# Sensirion_flowSensor.net
KiCad netlist of a schematic drawn in EAGLE
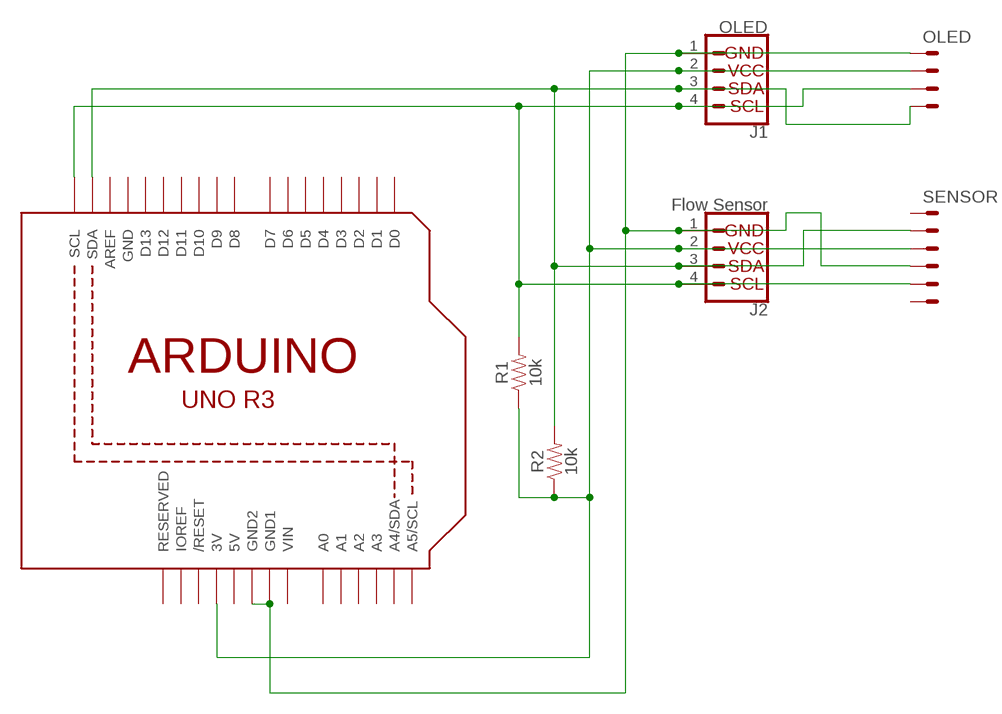
[diagram p0: schematic, sheet 1]

(export (version "E")
  (design (tool "Eeschema 10.0.6"))
  (components
    (comp (ref "FLOW")
      (value "SENSOR")
      (footprint "eagle-import:KK-156-6")
      (fields (field (name "MF") "MOLEX"))
      (libsource (lib "eagle-import") (part "KK-156-6"))
    )
    (comp (ref "J1")
      (value "OLED")
      (footprint "eagle-import:JST04_1MM_VERT")
      (libsource (lib "eagle-import") (part "QWIIC_CONNECTOR"))
    )
    (comp (ref "J2")
      (value "Flow Sensor")
      (footprint "eagle-import:JST04_1MM_VERT")
      (libsource (lib "eagle-import") (part "QWIIC_CONNECTOR"))
    )
    (comp (ref "OLED")
      (value "OLED")
      (footprint "eagle-import:KK-156-4")
      (fields (field (name "MF") "MOLEX"))
      (libsource (lib "eagle-import") (part "KK-156-4"))
    )
    (comp (ref "R1")
      (value "10k")
      (footprint "eagle-import:AXIAL-0.1")
      (libsource (lib "eagle-import") (part "10KOHM-VERT-1/4W-1%"))
    )
    (comp (ref "R2")
      (value "10k")
      (footprint "eagle-import:AXIAL-0.1")
      (libsource (lib "eagle-import") (part "10KOHM-VERT-1/4W-1%"))
    )
    (comp (ref "U1")
      (value "ARDUINOR3-BPLACE")
      (footprint "eagle-import:ARDUINOR3-BPLACE")
      (libsource (lib "eagle-import") (part "ARDUINOR3-BPLACE"))
    )
  )
  (nets
    (net (code "1") (name "/5V") (class "Default")
      (node (ref "U1") (pin "5V") (pinfunction "5V_5V") (pintype "power_in"))
    )
    (net (code "2") (name "/GND") (class "Default")
      (node (ref "U1") (pin "GND") (pinfunction "GND_GND") (pintype "power_in"))
    )
    (net (code "3") (name "/VIN") (class "Default")
      (node (ref "U1") (pin "VIN") (pinfunction "VIN_VIN") (pintype "power_in"))
    )
    (net (code "4") (name "Net-(FLOWB-S)") (class "Default")
      (node (ref "FLOW") (pin "2") (pinfunction "S_2") (pintype "passive"))
      (node (ref "J1") (pin "3") (pinfunction "3_3") (pintype "passive"))
      (node (ref "J2") (pin "3") (pinfunction "3_3") (pintype "passive"))
      (node (ref "OLED") (pin "4") (pinfunction "S_4") (pintype "passive"))
      (node (ref "R2") (pin "P$2") (pinfunction "2_P$2") (pintype "passive"))
      (node (ref "U1") (pin "SDA") (pinfunction "SDA_SDA") (pintype "bidirectional"))
    )
    (net (code "5") (name "Net-(FLOWC-S)") (class "Default")
      (node (ref "FLOW") (pin "3") (pinfunction "S_3") (pintype "passive"))
      (node (ref "J1") (pin "2") (pinfunction "2_2") (pintype "power_in"))
      (node (ref "J2") (pin "2") (pinfunction "2_2") (pintype "power_in"))
      (node (ref "OLED") (pin "2") (pinfunction "S_2") (pintype "passive"))
      (node (ref "R1") (pin "P$1") (pinfunction "1_P$1") (pintype "passive"))
      (node (ref "R2") (pin "P$1") (pinfunction "1_P$1") (pintype "passive"))
      (node (ref "U1") (pin "3V") (pinfunction "3V_3V") (pintype "power_in"))
    )
    (net (code "6") (name "Net-(FLOWD-S)") (class "Default")
      (node (ref "FLOW") (pin "4") (pinfunction "S_4") (pintype "passive"))
      (node (ref "J1") (pin "1") (pinfunction "1_1") (pintype "power_in"))
      (node (ref "J2") (pin "1") (pinfunction "1_1") (pintype "power_in"))
      (node (ref "OLED") (pin "1") (pinfunction "S_1") (pintype "passive"))
      (node (ref "U1") (pin "GND1") (pinfunction "GND1_GND1") (pintype "power_in"))
      (node (ref "U1") (pin "GND2") (pinfunction "GND2_GND2") (pintype "power_in"))
    )
    (net (code "7") (name "Net-(FLOWE-S)") (class "Default")
      (node (ref "FLOW") (pin "5") (pinfunction "S_5") (pintype "passive"))
      (node (ref "J1") (pin "4") (pinfunction "4_4") (pintype "passive"))
      (node (ref "J2") (pin "4") (pinfunction "4_4") (pintype "passive"))
      (node (ref "OLED") (pin "3") (pinfunction "S_3") (pintype "passive"))
      (node (ref "R1") (pin "P$2") (pinfunction "2_P$2") (pintype "passive"))
      (node (ref "U1") (pin "SCL") (pinfunction "SCL_SCL") (pintype "bidirectional"))
    )
    (net (code "8") (name "unconnected-(FLOWA-S-Pad1)") (class "Default")
      (node (ref "FLOW") (pin "1") (pinfunction "S_1") (pintype "passive"))
    )
    (net (code "9") (name "unconnected-(FLOWF-S-Pad6)") (class "Default")
      (node (ref "FLOW") (pin "6") (pinfunction "S_6") (pintype "passive"))
    )
    (net (code "10") (name "unconnected-(U1-A4{slash}SDA-PadA4)") (class "Default")
      (node (ref "U1") (pin "A4") (pinfunction "A4/SDA_A4") (pintype "bidirectional"))
    )
    (net (code "11") (name "unconnected-(U1-A5{slash}SCL-PadA5)") (class "Default")
      (node (ref "U1") (pin "A5") (pinfunction "A5/SCL_A5") (pintype "bidirectional"))
    )
    (net (code "12") (name "unconnected-(U1-PadA0)") (class "Default")
      (node (ref "U1") (pin "A0") (pinfunction "A0_A0") (pintype "bidirectional"))
    )
    (net (code "13") (name "unconnected-(U1-PadA1)") (class "Default")
      (node (ref "U1") (pin "A1") (pinfunction "A1_A1") (pintype "bidirectional"))
    )
    (net (code "14") (name "unconnected-(U1-PadA2)") (class "Default")
      (node (ref "U1") (pin "A2") (pinfunction "A2_A2") (pintype "bidirectional"))
    )
    (net (code "15") (name "unconnected-(U1-PadA3)") (class "Default")
      (node (ref "U1") (pin "A3") (pinfunction "A3_A3") (pintype "bidirectional"))
    )
    (net (code "16") (name "unconnected-(U1-PadAREF)") (class "Default")
      (node (ref "U1") (pin "AREF") (pinfunction "AREF_AREF") (pintype "bidirectional"))
    )
    (net (code "17") (name "unconnected-(U1-PadD0)") (class "Default")
      (node (ref "U1") (pin "D0") (pinfunction "D0_D0") (pintype "bidirectional"))
    )
    (net (code "18") (name "unconnected-(U1-PadD1)") (class "Default")
      (node (ref "U1") (pin "D1") (pinfunction "D1_D1") (pintype "bidirectional"))
    )
    (net (code "19") (name "unconnected-(U1-PadD2)") (class "Default")
      (node (ref "U1") (pin "D2") (pinfunction "D2_D2") (pintype "bidirectional"))
    )
    (net (code "20") (name "unconnected-(U1-PadD3)") (class "Default")
      (node (ref "U1") (pin "D3") (pinfunction "D3_D3") (pintype "bidirectional"))
    )
    (net (code "21") (name "unconnected-(U1-PadD4)") (class "Default")
      (node (ref "U1") (pin "D4") (pinfunction "D4_D4") (pintype "bidirectional"))
    )
    (net (code "22") (name "unconnected-(U1-PadD5)") (class "Default")
      (node (ref "U1") (pin "D5") (pinfunction "D5_D5") (pintype "bidirectional"))
    )
    (net (code "23") (name "unconnected-(U1-PadD6)") (class "Default")
      (node (ref "U1") (pin "D6") (pinfunction "D6_D6") (pintype "bidirectional"))
    )
    (net (code "24") (name "unconnected-(U1-PadD7)") (class "Default")
      (node (ref "U1") (pin "D7") (pinfunction "D7_D7") (pintype "bidirectional"))
    )
    (net (code "25") (name "unconnected-(U1-PadD8)") (class "Default")
      (node (ref "U1") (pin "D8") (pinfunction "D8_D8") (pintype "bidirectional"))
    )
    (net (code "26") (name "unconnected-(U1-PadD9)") (class "Default")
      (node (ref "U1") (pin "D9") (pinfunction "D9_D9") (pintype "bidirectional"))
    )
    (net (code "27") (name "unconnected-(U1-PadD10)") (class "Default")
      (node (ref "U1") (pin "D10") (pinfunction "D10_D10") (pintype "bidirectional"))
    )
    (net (code "28") (name "unconnected-(U1-PadD11)") (class "Default")
      (node (ref "U1") (pin "D11") (pinfunction "D11_D11") (pintype "bidirectional"))
    )
    (net (code "29") (name "unconnected-(U1-PadD12)") (class "Default")
      (node (ref "U1") (pin "D12") (pinfunction "D12_D12") (pintype "bidirectional"))
    )
    (net (code "30") (name "unconnected-(U1-PadD13)") (class "Default")
      (node (ref "U1") (pin "D13") (pinfunction "D13_D13") (pintype "bidirectional"))
    )
    (net (code "31") (name "unconnected-(U1-PadIOREF)") (class "Default")
      (node (ref "U1") (pin "IOREF") (pinfunction "IOREF_IOREF") (pintype "output"))
    )
    (net (code "32") (name "unconnected-(U1-PadRESERVED)") (class "Default")
      (node (ref "U1") (pin "RESERVED") (pinfunction "RESERVED_RESERVED") (pintype "no_connect"))
    )
    (net (code "33") (name "unconnected-(U1-{slash}RESET-PadRESET)") (class "Default")
      (node (ref "U1") (pin "RESET") (pinfunction "/RESET_RESET") (pintype "bidirectional"))
    )
  )
)
